# disaster01.net
KiCad netlist of a schematic drawn in EAGLE
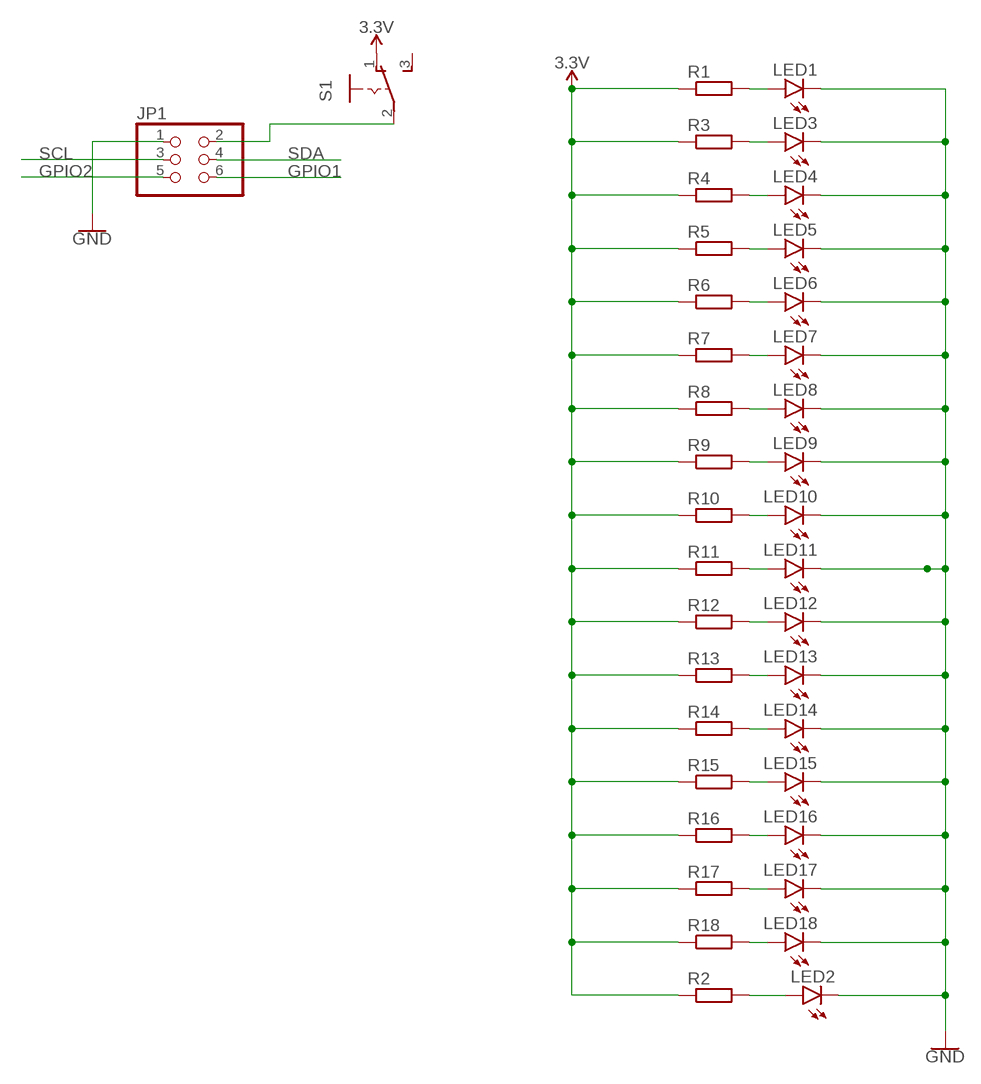
[diagram p0: schematic, sheet 1]

(export (version "E")
  (design (tool "Eeschema 10.0.6"))
  (components
    (comp (ref "JP1")
      (value "PINHD-2X3")
      (footprint "eagle-import:2X03")
      (libsource (lib "eagle-import") (part "PINHD-2X3"))
    )
    (comp (ref "LED1")
      (value "LED3MM")
      (footprint "eagle-import:LED3MM")
      (libsource (lib "eagle-import") (part "LED3MM"))
    )
    (comp (ref "LED2")
      (value "LED10MM")
      (footprint "eagle-import:LED10MM")
      (libsource (lib "eagle-import") (part "LED10MM"))
    )
    (comp (ref "LED3")
      (value "LED3MM")
      (footprint "eagle-import:LED3MM")
      (libsource (lib "eagle-import") (part "LED3MM"))
    )
    (comp (ref "LED4")
      (value "LED3MM")
      (footprint "eagle-import:LED3MM")
      (libsource (lib "eagle-import") (part "LED3MM"))
    )
    (comp (ref "LED5")
      (value "LED3MM")
      (footprint "eagle-import:LED3MM")
      (libsource (lib "eagle-import") (part "LED3MM"))
    )
    (comp (ref "LED6")
      (value "LED3MM")
      (footprint "eagle-import:LED3MM")
      (libsource (lib "eagle-import") (part "LED3MM"))
    )
    (comp (ref "LED7")
      (value "LED3MM")
      (footprint "eagle-import:LED3MM")
      (libsource (lib "eagle-import") (part "LED3MM"))
    )
    (comp (ref "LED8")
      (value "LED3MM")
      (footprint "eagle-import:LED3MM")
      (libsource (lib "eagle-import") (part "LED3MM"))
    )
    (comp (ref "LED9")
      (value "LED3MM")
      (footprint "eagle-import:LED3MM")
      (libsource (lib "eagle-import") (part "LED3MM"))
    )
    (comp (ref "LED10")
      (value "LED3MM")
      (footprint "eagle-import:LED3MM")
      (libsource (lib "eagle-import") (part "LED3MM"))
    )
    (comp (ref "LED11")
      (value "LED3MM")
      (footprint "eagle-import:LED3MM")
      (libsource (lib "eagle-import") (part "LED3MM"))
    )
    (comp (ref "LED12")
      (value "LED3MM")
      (footprint "eagle-import:LED3MM")
      (libsource (lib "eagle-import") (part "LED3MM"))
    )
    (comp (ref "LED13")
      (value "LED3MM")
      (footprint "eagle-import:LED3MM")
      (libsource (lib "eagle-import") (part "LED3MM"))
    )
    (comp (ref "LED14")
      (value "LED3MM")
      (footprint "eagle-import:LED3MM")
      (libsource (lib "eagle-import") (part "LED3MM"))
    )
    (comp (ref "LED15")
      (value "LED3MM")
      (footprint "eagle-import:LED3MM")
      (libsource (lib "eagle-import") (part "LED3MM"))
    )
    (comp (ref "LED16")
      (value "LED3MM")
      (footprint "eagle-import:LED3MM")
      (libsource (lib "eagle-import") (part "LED3MM"))
    )
    (comp (ref "LED17")
      (value "LED3MM")
      (footprint "eagle-import:LED3MM")
      (libsource (lib "eagle-import") (part "LED3MM"))
    )
    (comp (ref "LED18")
      (value "LED10MM")
      (footprint "eagle-import:LED10MM")
      (libsource (lib "eagle-import") (part "LED10MM"))
    )
    (comp (ref "R1")
      (value "R-EU_R0402")
      (footprint "eagle-import:R0402")
      (libsource (lib "eagle-import") (part "R-EU_R0402"))
    )
    (comp (ref "R2")
      (value "R-EU_R0402")
      (footprint "eagle-import:R0402")
      (libsource (lib "eagle-import") (part "R-EU_R0402"))
    )
    (comp (ref "R3")
      (value "R-EU_R0402")
      (footprint "eagle-import:R0402")
      (libsource (lib "eagle-import") (part "R-EU_R0402"))
    )
    (comp (ref "R4")
      (value "R-EU_R0402")
      (footprint "eagle-import:R0402")
      (libsource (lib "eagle-import") (part "R-EU_R0402"))
    )
    (comp (ref "R5")
      (value "R-EU_R0402")
      (footprint "eagle-import:R0402")
      (libsource (lib "eagle-import") (part "R-EU_R0402"))
    )
    (comp (ref "R6")
      (value "R-EU_R0402")
      (footprint "eagle-import:R0402")
      (libsource (lib "eagle-import") (part "R-EU_R0402"))
    )
    (comp (ref "R7")
      (value "R-EU_R0402")
      (footprint "eagle-import:R0402")
      (libsource (lib "eagle-import") (part "R-EU_R0402"))
    )
    (comp (ref "R8")
      (value "R-EU_R0402")
      (footprint "eagle-import:R0402")
      (libsource (lib "eagle-import") (part "R-EU_R0402"))
    )
    (comp (ref "R9")
      (value "R-EU_R0402")
      (footprint "eagle-import:R0402")
      (libsource (lib "eagle-import") (part "R-EU_R0402"))
    )
    (comp (ref "R10")
      (value "R-EU_R0402")
      (footprint "eagle-import:R0402")
      (libsource (lib "eagle-import") (part "R-EU_R0402"))
    )
    (comp (ref "R11")
      (value "R-EU_R0402")
      (footprint "eagle-import:R0402")
      (libsource (lib "eagle-import") (part "R-EU_R0402"))
    )
    (comp (ref "R12")
      (value "R-EU_R0402")
      (footprint "eagle-import:R0402")
      (libsource (lib "eagle-import") (part "R-EU_R0402"))
    )
    (comp (ref "R13")
      (value "R-EU_R0402")
      (footprint "eagle-import:R0402")
      (libsource (lib "eagle-import") (part "R-EU_R0402"))
    )
    (comp (ref "R14")
      (value "R-EU_R0402")
      (footprint "eagle-import:R0402")
      (libsource (lib "eagle-import") (part "R-EU_R0402"))
    )
    (comp (ref "R15")
      (value "R-EU_R0402")
      (footprint "eagle-import:R0402")
      (libsource (lib "eagle-import") (part "R-EU_R0402"))
    )
    (comp (ref "R16")
      (value "R-EU_R0402")
      (footprint "eagle-import:R0402")
      (libsource (lib "eagle-import") (part "R-EU_R0402"))
    )
    (comp (ref "R17")
      (value "R-EU_R0402")
      (footprint "eagle-import:R0402")
      (libsource (lib "eagle-import") (part "R-EU_R0402"))
    )
    (comp (ref "R18")
      (value "R-EU_R0402")
      (footprint "eagle-import:R0402")
      (libsource (lib "eagle-import") (part "R-EU_R0402"))
    )
    (comp (ref "S1")
      (value "255SB")
      (footprint "eagle-import:255SB")
      (libsource (lib "eagle-import") (part "255SB"))
    )
  )
  (nets
    (net (code "1") (name "/GPIO1") (class "Default")
      (node (ref "JP1") (pin "6") (pinfunction "6_6") (pintype "passive"))
    )
    (net (code "2") (name "/GPIO2") (class "Default")
      (node (ref "JP1") (pin "5") (pinfunction "5_5") (pintype "passive"))
    )
    (net (code "3") (name "/SCL") (class "Default")
      (node (ref "JP1") (pin "3") (pinfunction "3_3") (pintype "passive"))
    )
    (net (code "4") (name "/SDA") (class "Default")
      (node (ref "JP1") (pin "4") (pinfunction "4_4") (pintype "passive"))
    )
    (net (code "5") (name "3.3V") (class "Default")
      (node (ref "R1") (pin "1") (pinfunction "1_1") (pintype "passive"))
      (node (ref "R10") (pin "1") (pinfunction "1_1") (pintype "passive"))
      (node (ref "R11") (pin "1") (pinfunction "1_1") (pintype "passive"))
      (node (ref "R12") (pin "1") (pinfunction "1_1") (pintype "passive"))
      (node (ref "R13") (pin "1") (pinfunction "1_1") (pintype "passive"))
      (node (ref "R14") (pin "1") (pinfunction "1_1") (pintype "passive"))
      (node (ref "R15") (pin "1") (pinfunction "1_1") (pintype "passive"))
      (node (ref "R16") (pin "1") (pinfunction "1_1") (pintype "passive"))
      (node (ref "R17") (pin "1") (pinfunction "1_1") (pintype "passive"))
      (node (ref "R18") (pin "1") (pinfunction "1_1") (pintype "passive"))
      (node (ref "R2") (pin "1") (pinfunction "1_1") (pintype "passive"))
      (node (ref "R3") (pin "1") (pinfunction "1_1") (pintype "passive"))
      (node (ref "R4") (pin "1") (pinfunction "1_1") (pintype "passive"))
      (node (ref "R5") (pin "1") (pinfunction "1_1") (pintype "passive"))
      (node (ref "R6") (pin "1") (pinfunction "1_1") (pintype "passive"))
      (node (ref "R7") (pin "1") (pinfunction "1_1") (pintype "passive"))
      (node (ref "R8") (pin "1") (pinfunction "1_1") (pintype "passive"))
      (node (ref "R9") (pin "1") (pinfunction "1_1") (pintype "passive"))
      (node (ref "S1") (pin "1") (pinfunction "O_1") (pintype "passive"))
    )
    (net (code "6") (name "GND") (class "Default")
      (node (ref "JP1") (pin "1") (pinfunction "1_1") (pintype "passive"))
      (node (ref "LED1") (pin "K") (pinfunction "C_K") (pintype "passive"))
      (node (ref "LED10") (pin "K") (pinfunction "C_K") (pintype "passive"))
      (node (ref "LED11") (pin "K") (pinfunction "C_K") (pintype "passive"))
      (node (ref "LED12") (pin "K") (pinfunction "C_K") (pintype "passive"))
      (node (ref "LED13") (pin "K") (pinfunction "C_K") (pintype "passive"))
      (node (ref "LED14") (pin "K") (pinfunction "C_K") (pintype "passive"))
      (node (ref "LED15") (pin "K") (pinfunction "C_K") (pintype "passive"))
      (node (ref "LED16") (pin "K") (pinfunction "C_K") (pintype "passive"))
      (node (ref "LED17") (pin "K") (pinfunction "C_K") (pintype "passive"))
      (node (ref "LED18") (pin "K") (pinfunction "C_K") (pintype "passive"))
      (node (ref "LED2") (pin "K") (pinfunction "C_K") (pintype "passive"))
      (node (ref "LED3") (pin "K") (pinfunction "C_K") (pintype "passive"))
      (node (ref "LED4") (pin "K") (pinfunction "C_K") (pintype "passive"))
      (node (ref "LED5") (pin "K") (pinfunction "C_K") (pintype "passive"))
      (node (ref "LED6") (pin "K") (pinfunction "C_K") (pintype "passive"))
      (node (ref "LED7") (pin "K") (pinfunction "C_K") (pintype "passive"))
      (node (ref "LED8") (pin "K") (pinfunction "C_K") (pintype "passive"))
      (node (ref "LED9") (pin "K") (pinfunction "C_K") (pintype "passive"))
    )
    (net (code "7") (name "Net-(LED1-PadA)") (class "Default")
      (node (ref "LED1") (pin "A") (pinfunction "A_A") (pintype "passive"))
      (node (ref "R1") (pin "2") (pinfunction "2_2") (pintype "passive"))
    )
    (net (code "8") (name "Net-(LED2-PadA)") (class "Default")
      (node (ref "LED2") (pin "A") (pinfunction "A_A") (pintype "passive"))
      (node (ref "R2") (pin "2") (pinfunction "2_2") (pintype "passive"))
    )
    (net (code "9") (name "Net-(LED3-PadA)") (class "Default")
      (node (ref "LED3") (pin "A") (pinfunction "A_A") (pintype "passive"))
      (node (ref "R3") (pin "2") (pinfunction "2_2") (pintype "passive"))
    )
    (net (code "10") (name "Net-(LED4-PadA)") (class "Default")
      (node (ref "LED4") (pin "A") (pinfunction "A_A") (pintype "passive"))
      (node (ref "R4") (pin "2") (pinfunction "2_2") (pintype "passive"))
    )
    (net (code "11") (name "Net-(LED5-PadA)") (class "Default")
      (node (ref "LED5") (pin "A") (pinfunction "A_A") (pintype "passive"))
      (node (ref "R5") (pin "2") (pinfunction "2_2") (pintype "passive"))
    )
    (net (code "12") (name "Net-(LED6-PadA)") (class "Default")
      (node (ref "LED6") (pin "A") (pinfunction "A_A") (pintype "passive"))
      (node (ref "R6") (pin "2") (pinfunction "2_2") (pintype "passive"))
    )
    (net (code "13") (name "Net-(LED7-PadA)") (class "Default")
      (node (ref "LED7") (pin "A") (pinfunction "A_A") (pintype "passive"))
      (node (ref "R7") (pin "2") (pinfunction "2_2") (pintype "passive"))
    )
    (net (code "14") (name "Net-(LED8-PadA)") (class "Default")
      (node (ref "LED8") (pin "A") (pinfunction "A_A") (pintype "passive"))
      (node (ref "R8") (pin "2") (pinfunction "2_2") (pintype "passive"))
    )
    (net (code "15") (name "Net-(LED9-PadA)") (class "Default")
      (node (ref "LED9") (pin "A") (pinfunction "A_A") (pintype "passive"))
      (node (ref "R9") (pin "2") (pinfunction "2_2") (pintype "passive"))
    )
    (net (code "16") (name "Net-(LED10-PadA)") (class "Default")
      (node (ref "LED10") (pin "A") (pinfunction "A_A") (pintype "passive"))
      (node (ref "R10") (pin "2") (pinfunction "2_2") (pintype "passive"))
    )
    (net (code "17") (name "Net-(LED11-PadA)") (class "Default")
      (node (ref "LED11") (pin "A") (pinfunction "A_A") (pintype "passive"))
      (node (ref "R11") (pin "2") (pinfunction "2_2") (pintype "passive"))
    )
    (net (code "18") (name "Net-(LED12-PadA)") (class "Default")
      (node (ref "LED12") (pin "A") (pinfunction "A_A") (pintype "passive"))
      (node (ref "R12") (pin "2") (pinfunction "2_2") (pintype "passive"))
    )
    (net (code "19") (name "Net-(LED13-PadA)") (class "Default")
      (node (ref "LED13") (pin "A") (pinfunction "A_A") (pintype "passive"))
      (node (ref "R13") (pin "2") (pinfunction "2_2") (pintype "passive"))
    )
    (net (code "20") (name "Net-(LED14-PadA)") (class "Default")
      (node (ref "LED14") (pin "A") (pinfunction "A_A") (pintype "passive"))
      (node (ref "R14") (pin "2") (pinfunction "2_2") (pintype "passive"))
    )
    (net (code "21") (name "Net-(LED15-PadA)") (class "Default")
      (node (ref "LED15") (pin "A") (pinfunction "A_A") (pintype "passive"))
      (node (ref "R15") (pin "2") (pinfunction "2_2") (pintype "passive"))
    )
    (net (code "22") (name "Net-(LED16-PadA)") (class "Default")
      (node (ref "LED16") (pin "A") (pinfunction "A_A") (pintype "passive"))
      (node (ref "R16") (pin "2") (pinfunction "2_2") (pintype "passive"))
    )
    (net (code "23") (name "Net-(LED17-PadA)") (class "Default")
      (node (ref "LED17") (pin "A") (pinfunction "A_A") (pintype "passive"))
      (node (ref "R17") (pin "2") (pinfunction "2_2") (pintype "passive"))
    )
    (net (code "24") (name "Net-(LED18-PadA)") (class "Default")
      (node (ref "LED18") (pin "A") (pinfunction "A_A") (pintype "passive"))
      (node (ref "R18") (pin "2") (pinfunction "2_2") (pintype "passive"))
    )
    (net (code "25") (name "Net-(S1-P)") (class "Default")
      (node (ref "JP1") (pin "2") (pinfunction "2_2") (pintype "passive"))
      (node (ref "S1") (pin "2") (pinfunction "P_2") (pintype "passive"))
    )
    (net (code "26") (name "unconnected-(S1-S-Pad3)") (class "Default")
      (node (ref "S1") (pin "3") (pinfunction "S_3") (pintype "passive"))
    )
  )
)
